# mcu1_secondary.net
KiCad netlist of a schematic drawn in Altium Designer
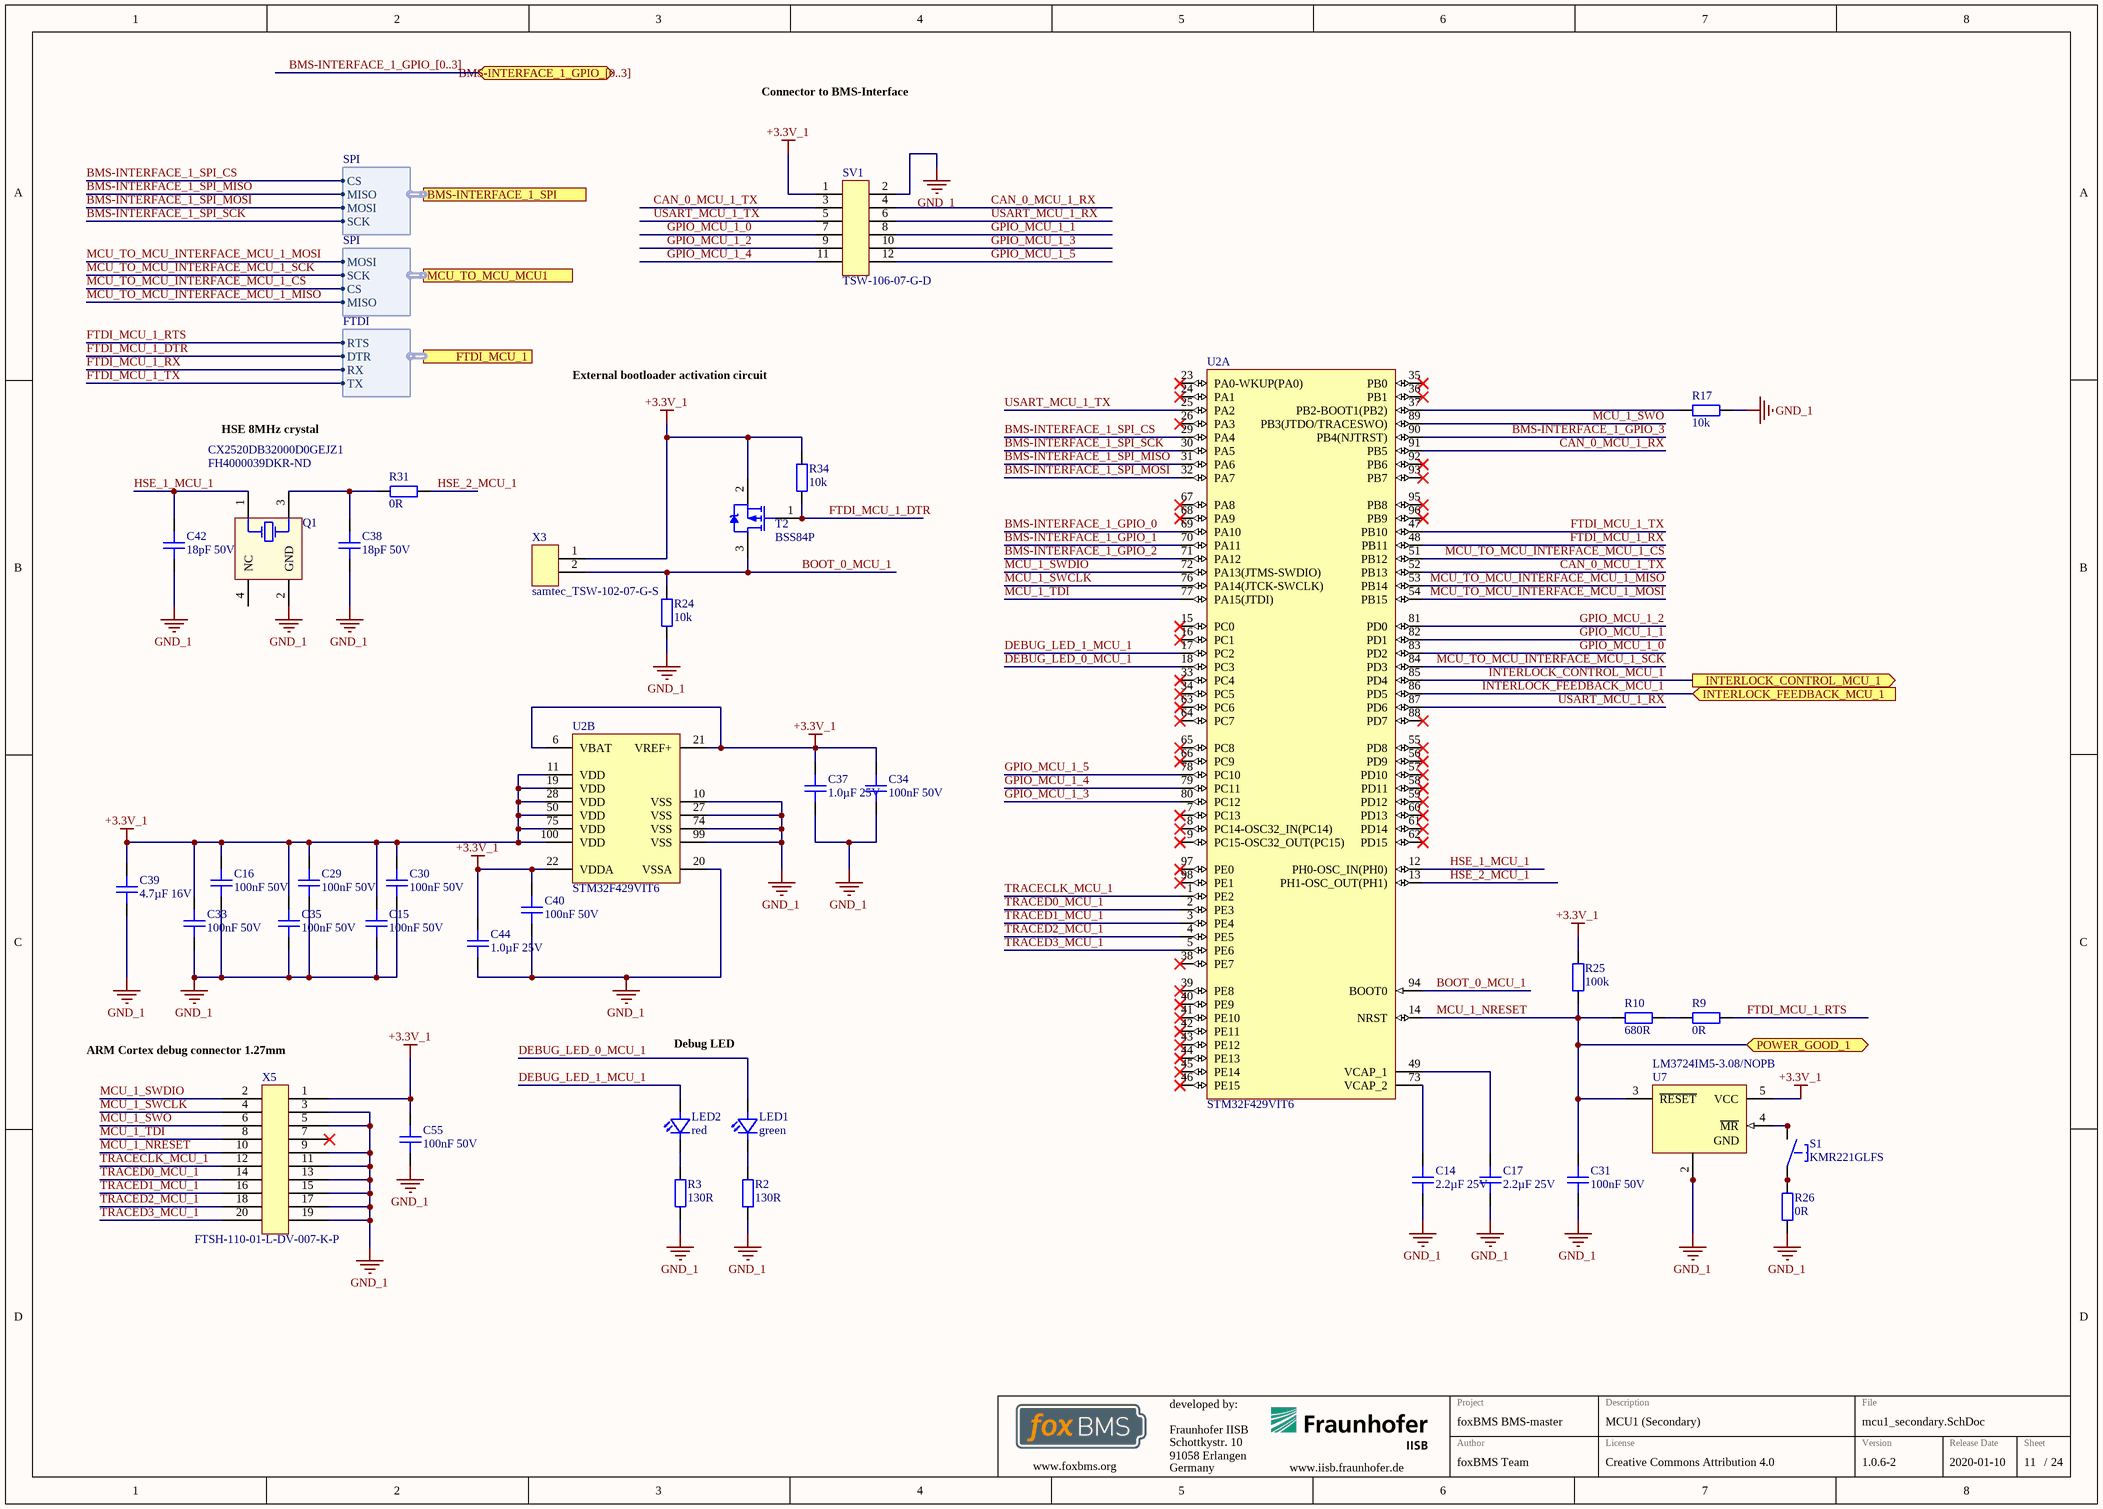
[diagram p0: mcu1_secondary.SchDoc]

(export (version "E")
  (design (tool "Eeschema 10.0.6"))
  (components
    (comp (ref "C14")
      (value "2.2µF 25V")
      (footprint "0805C")
      (description "Ceramic, 2.2µF, ±10%, 25V, X7R, –55 to 125°C, 0805 (2012),RoHS, Automotive")
      (fields (field (name "PART NUMBER") "GCJ21BR71E225KA01") (field (name "TOLERANCE") "±10%"))
      (libsource (lib "master-010106") (part "gen_C_ceramic_2u2_50V_X7R_0805"))
    )
    (comp (ref "C15")
      (value "100nF 50V")
      (footprint "0402C")
      (description "Ceramic, 100nF, ±10%, 50V, X7R, –55 to 125°C, 0402 (1005),RoHS, Automotive")
      (fields (field (name "PART NUMBER") "GCM155R71H104KE02") (field (name "TOLERANCE") "±10%"))
      (libsource (lib "master-010106") (part "gen_C_ceramic_100n_50V_X7R_0402"))
    )
    (comp (ref "C16")
      (value "100nF 50V")
      (footprint "0402C")
      (description "Ceramic, 100nF, ±10%, 50V, X7R, –55 to 125°C, 0402 (1005),RoHS, Automotive")
      (fields (field (name "PART NUMBER") "GCM155R71H104KE02") (field (name "TOLERANCE") "±10%"))
      (libsource (lib "master-010106") (part "gen_C_ceramic_100n_50V_X7R_0402"))
    )
    (comp (ref "C17")
      (value "2.2µF 25V")
      (footprint "0805C")
      (description "Ceramic, 2.2µF, ±10%, 25V, X7R, –55 to 125°C, 0805 (2012),RoHS, Automotive")
      (fields (field (name "PART NUMBER") "GCJ21BR71E225KA01") (field (name "TOLERANCE") "±10%"))
      (libsource (lib "master-010106") (part "gen_C_ceramic_2u2_50V_X7R_0805"))
    )
    (comp (ref "C29")
      (value "100nF 50V")
      (footprint "0402C")
      (description "Ceramic, 100nF, ±10%, 50V, X7R, –55 to 125°C, 0402 (1005),RoHS, Automotive")
      (fields (field (name "PART NUMBER") "GCM155R71H104KE02") (field (name "TOLERANCE") "±10%"))
      (libsource (lib "master-010106") (part "gen_C_ceramic_100n_50V_X7R_0402"))
    )
    (comp (ref "C30")
      (value "100nF 50V")
      (footprint "0402C")
      (description "Ceramic, 100nF, ±10%, 50V, X7R, –55 to 125°C, 0402 (1005),RoHS, Automotive")
      (fields (field (name "PART NUMBER") "GCM155R71H104KE02") (field (name "TOLERANCE") "±10%"))
      (libsource (lib "master-010106") (part "gen_C_ceramic_100n_50V_X7R_0402"))
    )
    (comp (ref "C31")
      (value "100nF 50V")
      (footprint "0603C")
      (description "Ceramic, 100nF, ±10%, 50V, X7R, –55 to 125°C, 0603 (1608),RoHS, Automotive")
      (fields (field (name "PART NUMBER") "GCJ188R71H104KA12") (field (name "TOLERANCE") "±10%"))
      (libsource (lib "master-010106") (part "C"))
    )
    (comp (ref "C33")
      (value "100nF 50V")
      (footprint "0402C")
      (description "Ceramic, 100nF, ±10%, 50V, X7R, –55 to 125°C, 0402 (1005),RoHS, Automotive")
      (fields (field (name "PART NUMBER") "GCM155R71H104KE02") (field (name "TOLERANCE") "±10%"))
      (libsource (lib "master-010106") (part "gen_C_ceramic_100n_50V_X7R_0402"))
    )
    (comp (ref "C34")
      (value "100nF 50V")
      (footprint "0402C")
      (description "Ceramic, 100nF, ±10%, 50V, X7R, –55 to 125°C, 0402 (1005),RoHS, Automotive")
      (fields (field (name "PART NUMBER") "GCM155R71H104KE02") (field (name "TOLERANCE") "±10%"))
      (libsource (lib "master-010106") (part "gen_C_ceramic_100n_50V_X7R_0402"))
    )
    (comp (ref "C35")
      (value "100nF 50V")
      (footprint "0402C")
      (description "Ceramic, 100nF, ±10%, 50V, X7R, –55 to 125°C, 0402 (1005),RoHS, Automotive")
      (fields (field (name "PART NUMBER") "GCM155R71H104KE02") (field (name "TOLERANCE") "±10%"))
      (libsource (lib "master-010106") (part "gen_C_ceramic_100n_50V_X7R_0402"))
    )
    (comp (ref "C37")
      (value "1.0µF 25V")
      (footprint "0603C")
      (description "Ceramic, 1.0µF, ±10%, 25V, X7R, –55 to 125°C, 0603 (1608),RoHS, Automotive")
      (fields (field (name "PART NUMBER") "GCJ188R71E105KA01") (field (name "TOLERANCE") "±10%"))
      (libsource (lib "master-010106") (part "gen_C_ceramic_1u_25V_X7R_0603"))
    )
    (comp (ref "C38")
      (value "18pF 50V")
      (footprint "0402C")
      (description "Ceramic, 18pF, ±5%, 50V, X7R, 25 to 125°C, 0402 (1005),RoHS, Automotive")
      (fields (field (name "PART NUMBER") "GCM1555C1H180JA16#") (field (name "TOLERANCE") "±5%"))
      (libsource (lib "master-010106") (part "gen_C_ceramic_18p_50V_C0G_0402"))
    )
    (comp (ref "C39")
      (value "4.7µF 16V")
      (footprint "0805C")
      (description "Ceramic, 4.7µF, ±10%, 16V, X7R, –55 to 125°C, 0805 (2012),RoHS, Automotive")
      (fields (field (name "PART NUMBER") "GCJ21BR71C475KA01") (field (name "TOLERANCE") "±10%"))
      (libsource (lib "master-010106") (part "gen_C_ceramic_4u7_16V_X7R_0805"))
    )
    (comp (ref "C40")
      (value "100nF 50V")
      (footprint "0402C")
      (description "Ceramic, 100nF, ±10%, 50V, X7R, –55 to 125°C, 0402 (1005),RoHS, Automotive")
      (fields (field (name "PART NUMBER") "GCM155R71H104KE02") (field (name "TOLERANCE") "±10%"))
      (libsource (lib "master-010106") (part "gen_C_ceramic_100n_50V_X7R_0402"))
    )
    (comp (ref "C42")
      (value "18pF 50V")
      (footprint "0402C")
      (description "Ceramic, 18pF, ±5%, 50V, X7R, 25 to 125°C, 0402 (1005),RoHS, Automotive")
      (fields (field (name "PART NUMBER") "GCM1555C1H180JA16#") (field (name "TOLERANCE") "±5%"))
      (libsource (lib "master-010106") (part "gen_C_ceramic_18p_50V_C0G_0402"))
    )
    (comp (ref "C44")
      (value "1.0µF 25V")
      (footprint "0603C")
      (description "Ceramic, 1.0µF, ±10%, 25V, X7R, –55 to 125°C, 0603 (1608),RoHS, Automotive")
      (fields (field (name "PART NUMBER") "GCJ188R71E105KA01") (field (name "TOLERANCE") "±10%"))
      (libsource (lib "master-010106") (part "gen_C_ceramic_1u_25V_X7R_0603"))
    )
    (comp (ref "C55")
      (value "100nF 50V")
      (footprint "0603C")
      (description "Ceramic, 100nF, ±10%, 50V, X7R, –55 to 125°C, 0603 (1608),RoHS, Automotive")
      (fields (field (name "PART NUMBER") "GCJ188R71H104KA12") (field (name "TOLERANCE") "±10%"))
      (libsource (lib "master-010106") (part "C"))
    )
    (comp (ref "LED1")
      (value "green")
      (footprint "LEDC1608X07N")
      (description "LED")
      (fields (field (name "PART NUMBER") "gen_LED_0603_green"))
      (libsource (lib "OE750") (part "D_LED"))
    )
    (comp (ref "LED2")
      (value "red")
      (footprint "LEDC1608X07N")
      (description "LED")
      (fields (field (name "PART NUMBER") "gen_LED_0603_red"))
      (libsource (lib "OE750") (part "D_LED"))
    )
    (comp (ref "Q1")
      (value "CX2520DB32000D0GEJZ1")
      (footprint "AVX-CX2520DB32000D0GEJZ1-4_V")
      (description "Crystal,CRYSTAL 40MHZ 15PF 85degC Surface Mount 2.5 x 2.0 mm")
      (fields
        (field (name "MANUFACTURER") "Kyocera")
        (field (name "SUPPLIER PART NUMBER 1") "FH4000039DKR-ND")
      )
      (libsource (lib "Altium Content Vault") (part "AVX-CX2520DB32000D0GEJZ1-4"))
    )
    (comp (ref "R2")
      (value "130R")
      (footprint "0603R")
      (description "SMD Resistor 130R 0603")
      (fields (field (name "PART NUMBER") "gen_R_130R_0603") (field (name "TOLERANCE") "1%"))
      (libsource (lib "master-010106") (part "R"))
    )
    (comp (ref "R3")
      (value "130R")
      (footprint "0603R")
      (description "SMD Resistor 130R 0603")
      (fields (field (name "PART NUMBER") "gen_R_130R_0603") (field (name "TOLERANCE") "1%"))
      (libsource (lib "master-010106") (part "R"))
    )
    (comp (ref "R9")
      (value "0R")
      (footprint "0603R")
      (description "SMD Resistor 0R 0603")
      (fields (field (name "PART NUMBER") "gen_R_0R_0603") (field (name "POWER") "0.1W"))
      (libsource (lib "master-010106") (part "R"))
    )
    (comp (ref "R10")
      (value "680R")
      (footprint "0603R")
      (description "SMD Resistor 680R 0603")
      (fields (field (name "PART NUMBER") "gen_R_680R_0603") (field (name "TOLERANCE") "1%"))
      (libsource (lib "master-010106") (part "R"))
    )
    (comp (ref "R17")
      (value "10k")
      (footprint "0603R")
      (description "SMD Resistor 10k 0603")
      (fields (field (name "PART NUMBER") "gen_R_10k_0603") (field (name "TOLERANCE") "1%"))
      (libsource (lib "master-010106") (part "R"))
    )
    (comp (ref "R24")
      (value "10k")
      (footprint "0603R")
      (description "SMD Resistor 10k 0603")
      (fields (field (name "PART NUMBER") "gen_R_10k_0603") (field (name "TOLERANCE") "1%"))
      (libsource (lib "master-010106") (part "R"))
    )
    (comp (ref "R25")
      (value "100k")
      (footprint "0603R")
      (description "SMD Resistor 100k 0603")
      (fields (field (name "PART NUMBER") "gen_R_100k_0603"))
      (libsource (lib "master-010106") (part "gen_R_100k_0603"))
    )
    (comp (ref "R26")
      (value "0R")
      (footprint "0603R")
      (description "SMD Resistor 0R 0603")
      (fields (field (name "PART NUMBER") "gen_R_0R_0603") (field (name "POWER") "0.1W"))
      (libsource (lib "master-010106") (part "R"))
    )
    (comp (ref "R31")
      (value "0R")
      (footprint "0402R")
      (description "SMD Resistor 0R 0402")
      (fields (field (name "PART NUMBER") "gen_R_0R_0402"))
      (libsource (lib "master-010106") (part "gen_R_0R_0402"))
    )
    (comp (ref "R34")
      (value "10k")
      (footprint "0603R")
      (description "SMD Resistor 10k 0603")
      (fields (field (name "PART NUMBER") "gen_R_10k_0603") (field (name "TOLERANCE") "1%"))
      (libsource (lib "master-010106") (part "R"))
    )
    (comp (ref "S1")
      (value "KMR221GLFS")
      (footprint "KMR2_Series")
      (description "Microminiature Tactile Switch")
      (fields (field (name "MANUFACTURER") "CK Components"))
      (libsource (lib "OE750") (part "Switch_4_Pin"))
    )
    (comp (ref "SV1")
      (value "TSW-106-07-G-D")
      (footprint "Pinheader_2.54_2x6")
      (description "Board-To-Board Connector, Vertical, 2.54 mm, 12 Contacts, Header, TSW Series, Through Hole, 2 Rows")
      (fields (field (name "MANUFACTURER") "Samtec"))
      (libsource (lib "OE750") (part "X2x6"))
    )
    (comp (ref "T2")
      (value "BSS84P")
      (footprint "INF-PG-SOT23_N")
      (fields (field (name "MANUFACTURER") "Infineon"))
      (libsource (lib "Altium Content Vault") (part "INF-PEMOS-GSD-3-B"))
    )
    (comp (ref "U2")
      (value "STM32F429VIT6")
      (footprint "STM-LQFP100_N")
      (fields (field (name "MANUFACTURER") "STMicroelectronics"))
      (libsource (lib "Altium Content Vault") (part "MC-ARM-STM32F4X9-SQ100"))
    )
    (comp (ref "U7")
      (value "LM3724IM5-3.08/NOPB")
      (footprint "MF05A_N")
      (description "5-Pin Microprocessor Reset Circuits, 5-pin SOT-23, Pb-Free")
      (fields (field (name "MANUFACTURER") "National Semiconductor"))
      (libsource (lib "Altium Content Vault") (part "PM-SCCT-LM3724-5"))
    )
    (comp (ref "X3")
      (value "samtec_TSW-102-07-G-S")
      (footprint "Pinheader_2.54_2")
      (description "Board-To-Board Connector, Vertical, 2.54 mm, 2 Contacts, Header, TSW Series, Through Hole, 1 Row")
      (fields (field (name "MANUFACTURER") "Samtec"))
      (libsource (lib "OE750") (part "X2"))
    )
    (comp (ref "X5")
      (value "FTSH-110-01-L-DV-007-K-P")
      (footprint "CORTEX_DEBUG_20_PIN")
      (description "Board-To-Board Connector, ARM Cortex Debug Header 20 Pin")
      (fields
        (field (name "PART NUMBER") "samtec_FTSH-110-01-L-DV-007-K-P")
        (field (name "MANUFACTURER") "Samtec")
      )
      (libsource (lib "OE750") (part "CORTEX_DEBUG_20_PIN"))
    )
  )
  (nets
    (net (code "3") (name "+3.3V_1") (class "Default")
      (node (ref "C15") (pin "1") (pinfunction "1_1") (pintype "passive"))
      (node (ref "C16") (pin "1") (pinfunction "1_1") (pintype "passive"))
      (node (ref "C29") (pin "1") (pinfunction "1_1") (pintype "passive"))
      (node (ref "C30") (pin "1") (pinfunction "1_1") (pintype "passive"))
      (node (ref "C33") (pin "1") (pinfunction "1_1") (pintype "passive"))
      (node (ref "C34") (pin "1") (pinfunction "1_1") (pintype "passive"))
      (node (ref "C35") (pin "1") (pinfunction "1_1") (pintype "passive"))
      (node (ref "C37") (pin "1") (pinfunction "1_1") (pintype "passive"))
      (node (ref "C39") (pin "1") (pinfunction "1_1") (pintype "passive"))
      (node (ref "C40") (pin "1") (pinfunction "1_1") (pintype "passive"))
      (node (ref "C44") (pin "1") (pinfunction "1_1") (pintype "passive"))
      (node (ref "C55") (pin "1") (pinfunction "1_1") (pintype "passive"))
      (node (ref "R25") (pin "2") (pinfunction "2_2") (pintype "passive"))
      (node (ref "R34") (pin "2") (pinfunction "2_2") (pintype "passive"))
      (node (ref "SV1") (pin "1") (pintype "passive"))
      (node (ref "T2") (pin "2") (pinfunction "SOURCE_2") (pintype "passive"))
      (node (ref "U2") (pin "100") (pinfunction "VDD_100") (pintype "power_in"))
      (node (ref "U2") (pin "11") (pinfunction "VDD_11") (pintype "power_in"))
      (node (ref "U2") (pin "19") (pinfunction "VDD_19") (pintype "power_in"))
      (node (ref "U2") (pin "21") (pinfunction "VREF+_21") (pintype "power_in"))
      (node (ref "U2") (pin "22") (pinfunction "VDDA_22") (pintype "power_in"))
      (node (ref "U2") (pin "28") (pinfunction "VDD_28") (pintype "power_in"))
      (node (ref "U2") (pin "50") (pinfunction "VDD_50") (pintype "power_in"))
      (node (ref "U2") (pin "6") (pinfunction "VBAT_6") (pintype "power_in"))
      (node (ref "U2") (pin "75") (pinfunction "VDD_75") (pintype "power_in"))
      (node (ref "U7") (pin "5") (pinfunction "VCC_5") (pintype "power_in"))
      (node (ref "X3") (pin "1") (pintype "passive"))
      (node (ref "X5") (pin "1") (pintype "passive"))
    )
    (net (code "4") (name "/BMS-INTERFACE_1_GPIO_0") (class "Default")
      (node (ref "U2") (pin "69") (pinfunction "PA10_69") (pintype "bidirectional"))
    )
    (net (code "5") (name "/BMS-INTERFACE_1_GPIO_1") (class "Default")
      (node (ref "U2") (pin "70") (pinfunction "PA11_70") (pintype "bidirectional"))
    )
    (net (code "6") (name "/BMS-INTERFACE_1_GPIO_2") (class "Default")
      (node (ref "U2") (pin "71") (pinfunction "PA12_71") (pintype "bidirectional"))
    )
    (net (code "7") (name "/BMS-INTERFACE_1_GPIO_3") (class "Default")
      (node (ref "U2") (pin "90") (pinfunction "PB4(NJTRST)_90") (pintype "bidirectional"))
    )
    (net (code "9") (name "/BMS-INTERFACE_1_SPI_CS") (class "Default")
      (node (ref "U2") (pin "29") (pinfunction "PA4_29") (pintype "bidirectional"))
    )
    (net (code "10") (name "/BMS-INTERFACE_1_SPI_MISO") (class "Default")
      (node (ref "U2") (pin "31") (pinfunction "PA6_31") (pintype "bidirectional"))
    )
    (net (code "11") (name "/BMS-INTERFACE_1_SPI_MOSI") (class "Default")
      (node (ref "U2") (pin "32") (pinfunction "PA7_32") (pintype "bidirectional"))
    )
    (net (code "12") (name "/BMS-INTERFACE_1_SPI_SCK") (class "Default")
      (node (ref "U2") (pin "30") (pinfunction "PA5_30") (pintype "bidirectional"))
    )
    (net (code "13") (name "/BOOT_0_MCU_1") (class "Default")
      (node (ref "R24") (pin "2") (pinfunction "2_2") (pintype "passive"))
      (node (ref "T2") (pin "3") (pinfunction "DRAIN_3") (pintype "passive"))
      (node (ref "U2") (pin "94") (pinfunction "BOOT0_94") (pintype "input"))
      (node (ref "X3") (pin "2") (pintype "passive"))
    )
    (net (code "14") (name "/CAN_0_MCU_1_RX") (class "Default")
      (node (ref "SV1") (pin "4") (pintype "passive"))
      (node (ref "U2") (pin "91") (pinfunction "PB5_91") (pintype "bidirectional"))
    )
    (net (code "15") (name "/CAN_0_MCU_1_TX") (class "Default")
      (node (ref "SV1") (pin "3") (pintype "passive"))
      (node (ref "U2") (pin "52") (pinfunction "PB13_52") (pintype "bidirectional"))
    )
    (net (code "16") (name "/DEBUG_LED_0_MCU_1") (class "Default")
      (node (ref "LED1") (pin "2") (pinfunction "A_2") (pintype "passive"))
      (node (ref "U2") (pin "18") (pinfunction "PC3_18") (pintype "bidirectional"))
    )
    (net (code "17") (name "/DEBUG_LED_1_MCU_1") (class "Default")
      (node (ref "LED2") (pin "2") (pinfunction "A_2") (pintype "passive"))
      (node (ref "U2") (pin "17") (pinfunction "PC2_17") (pintype "bidirectional"))
    )
    (net (code "18") (name "/FTDI_MCU_1_DTR") (class "Default")
      (node (ref "R34") (pin "1") (pinfunction "1_1") (pintype "passive"))
      (node (ref "T2") (pin "1") (pinfunction "GATE_1") (pintype "passive"))
    )
    (net (code "19") (name "/FTDI_MCU_1_RTS") (class "Default")
      (node (ref "R9") (pin "2") (pinfunction "2_2") (pintype "passive"))
    )
    (net (code "20") (name "/FTDI_MCU_1_RX") (class "Default")
      (node (ref "U2") (pin "48") (pinfunction "PB11_48") (pintype "bidirectional"))
    )
    (net (code "21") (name "/FTDI_MCU_1_TX") (class "Default")
      (node (ref "U2") (pin "47") (pinfunction "PB10_47") (pintype "bidirectional"))
    )
    (net (code "22") (name "/GPIO_MCU_1_0") (class "Default")
      (node (ref "SV1") (pin "7") (pintype "passive"))
      (node (ref "U2") (pin "83") (pinfunction "PD2_83") (pintype "bidirectional"))
    )
    (net (code "23") (name "/GPIO_MCU_1_1") (class "Default")
      (node (ref "SV1") (pin "8") (pintype "passive"))
      (node (ref "U2") (pin "82") (pinfunction "PD1_82") (pintype "bidirectional"))
    )
    (net (code "24") (name "/GPIO_MCU_1_2") (class "Default")
      (node (ref "SV1") (pin "9") (pintype "passive"))
      (node (ref "U2") (pin "81") (pinfunction "PD0_81") (pintype "bidirectional"))
    )
    (net (code "25") (name "/GPIO_MCU_1_3") (class "Default")
      (node (ref "SV1") (pin "10") (pintype "passive"))
      (node (ref "U2") (pin "80") (pinfunction "PC12_80") (pintype "bidirectional"))
    )
    (net (code "26") (name "/GPIO_MCU_1_4") (class "Default")
      (node (ref "SV1") (pin "11") (pintype "passive"))
      (node (ref "U2") (pin "79") (pinfunction "PC11_79") (pintype "bidirectional"))
    )
    (net (code "27") (name "/GPIO_MCU_1_5") (class "Default")
      (node (ref "SV1") (pin "12") (pintype "passive"))
      (node (ref "U2") (pin "78") (pinfunction "PC10_78") (pintype "bidirectional"))
    )
    (net (code "28") (name "/HSE_1_MCU_1") (class "Default")
      (node (ref "C42") (pin "2") (pinfunction "2_2") (pintype "passive"))
      (node (ref "Q1") (pin "1") (pinfunction "HOT_1") (pintype "passive"))
      (node (ref "U2") (pin "12") (pinfunction "PH0-OSC_IN(PH0)_12") (pintype "bidirectional"))
    )
    (net (code "29") (name "/HSE_2_MCU_1") (class "Default")
      (node (ref "R31") (pin "1") (pinfunction "1_1") (pintype "passive"))
      (node (ref "U2") (pin "13") (pinfunction "PH1-OSC_OUT(PH1)_13") (pintype "bidirectional"))
    )
    (net (code "30") (name "/INTERLOCK_CONTROL_MCU_1") (class "Default")
      (node (ref "U2") (pin "85") (pinfunction "PD4_85") (pintype "bidirectional"))
    )
    (net (code "31") (name "/INTERLOCK_FEEDBACK_MCU_1") (class "Default")
      (node (ref "U2") (pin "86") (pinfunction "PD5_86") (pintype "bidirectional"))
    )
    (net (code "32") (name "/MCU_1_NRESET") (class "Default")
      (node (ref "C31") (pin "1") (pinfunction "1_1") (pintype "passive"))
      (node (ref "R10") (pin "1") (pinfunction "1_1") (pintype "passive"))
      (node (ref "R25") (pin "1") (pinfunction "1_1") (pintype "passive"))
      (node (ref "U2") (pin "14") (pinfunction "NRST_14") (pintype "bidirectional"))
      (node (ref "U7") (pin "3") (pinfunction "~{RESET}_3") (pintype "open_collector"))
      (node (ref "X5") (pin "10") (pintype "passive"))
    )
    (net (code "33") (name "/MCU_1_SWCLK") (class "Default")
      (node (ref "U2") (pin "76") (pinfunction "PA14(JTCK-SWCLK)_76") (pintype "bidirectional"))
      (node (ref "X5") (pin "4") (pintype "passive"))
    )
    (net (code "34") (name "/MCU_1_SWDIO") (class "Default")
      (node (ref "U2") (pin "72") (pinfunction "PA13(JTMS-SWDIO)_72") (pintype "bidirectional"))
      (node (ref "X5") (pin "2") (pintype "passive"))
    )
    (net (code "35") (name "/MCU_1_SWO") (class "Default")
      (node (ref "U2") (pin "89") (pinfunction "PB3(JTDO/TRACESWO)_89") (pintype "bidirectional"))
      (node (ref "X5") (pin "6") (pintype "passive"))
    )
    (net (code "36") (name "/MCU_1_TDI") (class "Default")
      (node (ref "U2") (pin "77") (pinfunction "PA15(JTDI)_77") (pintype "bidirectional"))
      (node (ref "X5") (pin "8") (pintype "passive"))
    )
    (net (code "37") (name "/MCU_TO_MCU_INTERFACE_MCU_1_CS") (class "Default")
      (node (ref "U2") (pin "51") (pinfunction "PB12_51") (pintype "bidirectional"))
    )
    (net (code "38") (name "/MCU_TO_MCU_INTERFACE_MCU_1_MISO") (class "Default")
      (node (ref "U2") (pin "53") (pinfunction "PB14_53") (pintype "bidirectional"))
    )
    (net (code "39") (name "/MCU_TO_MCU_INTERFACE_MCU_1_MOSI") (class "Default")
      (node (ref "U2") (pin "54") (pinfunction "PB15_54") (pintype "bidirectional"))
    )
    (net (code "40") (name "/MCU_TO_MCU_INTERFACE_MCU_1_SCK") (class "Default")
      (node (ref "U2") (pin "84") (pinfunction "PD3_84") (pintype "bidirectional"))
    )
    (net (code "41") (name "/TRACECLK_MCU_1") (class "Default")
      (node (ref "U2") (pin "1") (pinfunction "PE2_1") (pintype "bidirectional"))
      (node (ref "X5") (pin "12") (pintype "passive"))
    )
    (net (code "42") (name "/TRACED0_MCU_1") (class "Default")
      (node (ref "U2") (pin "2") (pinfunction "PE3_2") (pintype "bidirectional"))
      (node (ref "X5") (pin "14") (pintype "passive"))
    )
    (net (code "43") (name "/TRACED1_MCU_1") (class "Default")
      (node (ref "U2") (pin "3") (pinfunction "PE4_3") (pintype "bidirectional"))
      (node (ref "X5") (pin "16") (pintype "passive"))
    )
    (net (code "44") (name "/TRACED2_MCU_1") (class "Default")
      (node (ref "U2") (pin "4") (pinfunction "PE5_4") (pintype "bidirectional"))
      (node (ref "X5") (pin "18") (pintype "passive"))
    )
    (net (code "45") (name "/TRACED3_MCU_1") (class "Default")
      (node (ref "U2") (pin "5") (pinfunction "PE6_5") (pintype "bidirectional"))
      (node (ref "X5") (pin "20") (pintype "passive"))
    )
    (net (code "46") (name "/USART_MCU_1_RX") (class "Default")
      (node (ref "SV1") (pin "6") (pintype "passive"))
      (node (ref "U2") (pin "87") (pinfunction "PD6_87") (pintype "bidirectional"))
    )
    (net (code "47") (name "/USART_MCU_1_TX") (class "Default")
      (node (ref "SV1") (pin "5") (pintype "passive"))
      (node (ref "U2") (pin "25") (pinfunction "PA2_25") (pintype "bidirectional"))
    )
    (net (code "50") (name "GND_1") (class "Default")
      (node (ref "C14") (pin "2") (pinfunction "2_2") (pintype "passive"))
      (node (ref "C15") (pin "2") (pinfunction "2_2") (pintype "passive"))
      (node (ref "C16") (pin "2") (pinfunction "2_2") (pintype "passive"))
      (node (ref "C17") (pin "2") (pinfunction "2_2") (pintype "passive"))
      (node (ref "C29") (pin "2") (pinfunction "2_2") (pintype "passive"))
      (node (ref "C30") (pin "2") (pinfunction "2_2") (pintype "passive"))
      (node (ref "C31") (pin "2") (pinfunction "2_2") (pintype "passive"))
      (node (ref "C33") (pin "2") (pinfunction "2_2") (pintype "passive"))
      (node (ref "C34") (pin "2") (pinfunction "2_2") (pintype "passive"))
      (node (ref "C35") (pin "2") (pinfunction "2_2") (pintype "passive"))
      (node (ref "C37") (pin "2") (pinfunction "2_2") (pintype "passive"))
      (node (ref "C38") (pin "2") (pinfunction "2_2") (pintype "passive"))
      (node (ref "C39") (pin "2") (pinfunction "2_2") (pintype "passive"))
      (node (ref "C40") (pin "2") (pinfunction "2_2") (pintype "passive"))
      (node (ref "C42") (pin "1") (pinfunction "1_1") (pintype "passive"))
      (node (ref "C44") (pin "2") (pinfunction "2_2") (pintype "passive"))
      (node (ref "C55") (pin "2") (pinfunction "2_2") (pintype "passive"))
      (node (ref "Q1") (pin "2") (pinfunction "GND_2") (pintype "power_in"))
      (node (ref "R17") (pin "1") (pinfunction "1_1") (pintype "passive"))
      (node (ref "R2") (pin "1") (pinfunction "1_1") (pintype "passive"))
      (node (ref "R24") (pin "1") (pinfunction "1_1") (pintype "passive"))
      (node (ref "R26") (pin "1") (pinfunction "1_1") (pintype "passive"))
      (node (ref "R3") (pin "1") (pinfunction "1_1") (pintype "passive"))
      (node (ref "SV1") (pin "2") (pintype "passive"))
      (node (ref "U2") (pin "10") (pinfunction "VSS_10") (pintype "power_in"))
      (node (ref "U2") (pin "20") (pinfunction "VSSA_20") (pintype "power_in"))
      (node (ref "U2") (pin "27") (pinfunction "VSS_27") (pintype "power_in"))
      (node (ref "U2") (pin "74") (pinfunction "VSS_74") (pintype "power_in"))
      (node (ref "U2") (pin "99") (pinfunction "VSS_99") (pintype "power_in"))
      (node (ref "U7") (pin "1") (pinfunction "GND_1") (pintype "power_in"))
      (node (ref "U7") (pin "2") (pinfunction "GND_2") (pintype "power_in"))
      (node (ref "X5") (pin "11") (pintype "passive"))
      (node (ref "X5") (pin "13") (pintype "passive"))
      (node (ref "X5") (pin "15") (pintype "passive"))
      (node (ref "X5") (pin "17") (pintype "passive"))
      (node (ref "X5") (pin "19") (pintype "passive"))
      (node (ref "X5") (pin "3") (pintype "passive"))
      (node (ref "X5") (pin "5") (pintype "passive"))
      (node (ref "X5") (pin "9") (pintype "passive"))
    )
    (net (code "51") (name "Net-(C38-Pad1)") (class "Default")
      (node (ref "C38") (pin "1") (pinfunction "1_1") (pintype "passive"))
      (node (ref "Q1") (pin "3") (pinfunction "HOT_3") (pintype "passive"))
      (node (ref "R31") (pin "2") (pinfunction "2_2") (pintype "passive"))
    )
    (net (code "52") (name "Net-(LED1-C)") (class "Default")
      (node (ref "LED1") (pin "1") (pinfunction "C_1") (pintype "passive"))
      (node (ref "R2") (pin "2") (pinfunction "2_2") (pintype "passive"))
    )
    (net (code "53") (name "Net-(LED2-C)") (class "Default")
      (node (ref "LED2") (pin "1") (pinfunction "C_1") (pintype "passive"))
      (node (ref "R3") (pin "2") (pinfunction "2_2") (pintype "passive"))
    )
    (net (code "54") (name "Net-(R10-Pad2)") (class "Default")
      (node (ref "R10") (pin "2") (pinfunction "2_2") (pintype "passive"))
      (node (ref "R9") (pin "1") (pinfunction "1_1") (pintype "passive"))
    )
    (net (code "55") (name "Net-(R26-Pad2)") (class "Default")
      (node (ref "R26") (pin "2") (pinfunction "2_2") (pintype "passive"))
      (node (ref "S1") (pin "1") (pintype "passive"))
      (node (ref "S1") (pin "2") (pintype "passive"))
    )
    (net (code "56") (name "Net-(U2A-PB2-BOOT1(PB2))") (class "Default")
      (node (ref "R17") (pin "2") (pinfunction "2_2") (pintype "passive"))
      (node (ref "U2") (pin "37") (pinfunction "PB2-BOOT1(PB2)_37") (pintype "bidirectional"))
    )
    (net (code "57") (name "Net-(U2A-VCAP_1)") (class "Default")
      (node (ref "C17") (pin "1") (pinfunction "1_1") (pintype "passive"))
      (node (ref "U2") (pin "49") (pinfunction "VCAP_1_49") (pintype "power_in"))
    )
    (net (code "58") (name "Net-(U2A-VCAP_2)") (class "Default")
      (node (ref "C14") (pin "1") (pinfunction "1_1") (pintype "passive"))
      (node (ref "U2") (pin "73") (pinfunction "VCAP_2_73") (pintype "power_in"))
    )
    (net (code "59") (name "Net-(U7-~{MR})") (class "Default")
      (node (ref "S1") (pin "3") (pintype "passive"))
      (node (ref "S1") (pin "4") (pintype "passive"))
      (node (ref "U7") (pin "4") (pinfunction "~{MR}_4") (pintype "input"))
    )
    (net (code "60") (name "unconnected-(Q1-NC-Pad4)") (class "Default")
      (node (ref "Q1") (pin "4") (pinfunction "NC_4") (pintype "passive"))
    )
    (net (code "61") (name "unconnected-(U2A-PA0-WKUP(PA0)-Pad23)") (class "Default")
      (node (ref "U2") (pin "23") (pinfunction "PA0-WKUP(PA0)_23") (pintype "bidirectional+no_connect"))
    )
    (net (code "62") (name "unconnected-(U2A-PA1-Pad24)") (class "Default")
      (node (ref "U2") (pin "24") (pinfunction "PA1_24") (pintype "bidirectional+no_connect"))
    )
    (net (code "63") (name "unconnected-(U2A-PA3-Pad26)") (class "Default")
      (node (ref "U2") (pin "26") (pinfunction "PA3_26") (pintype "bidirectional+no_connect"))
    )
    (net (code "64") (name "unconnected-(U2A-PA8-Pad67)") (class "Default")
      (node (ref "U2") (pin "67") (pinfunction "PA8_67") (pintype "bidirectional+no_connect"))
    )
    (net (code "65") (name "unconnected-(U2A-PA9-Pad68)") (class "Default")
      (node (ref "U2") (pin "68") (pinfunction "PA9_68") (pintype "bidirectional+no_connect"))
    )
    (net (code "66") (name "unconnected-(U2A-PB0-Pad35)") (class "Default")
      (node (ref "U2") (pin "35") (pinfunction "PB0_35") (pintype "bidirectional+no_connect"))
    )
    (net (code "67") (name "unconnected-(U2A-PB1-Pad36)") (class "Default")
      (node (ref "U2") (pin "36") (pinfunction "PB1_36") (pintype "bidirectional+no_connect"))
    )
    (net (code "68") (name "unconnected-(U2A-PB6-Pad92)") (class "Default")
      (node (ref "U2") (pin "92") (pinfunction "PB6_92") (pintype "bidirectional+no_connect"))
    )
    (net (code "69") (name "unconnected-(U2A-PB7-Pad93)") (class "Default")
      (node (ref "U2") (pin "93") (pinfunction "PB7_93") (pintype "bidirectional+no_connect"))
    )
    (net (code "70") (name "unconnected-(U2A-PB8-Pad95)") (class "Default")
      (node (ref "U2") (pin "95") (pinfunction "PB8_95") (pintype "bidirectional+no_connect"))
    )
    (net (code "71") (name "unconnected-(U2A-PB9-Pad96)") (class "Default")
      (node (ref "U2") (pin "96") (pinfunction "PB9_96") (pintype "bidirectional+no_connect"))
    )
    (net (code "72") (name "unconnected-(U2A-PC0-Pad15)") (class "Default")
      (node (ref "U2") (pin "15") (pinfunction "PC0_15") (pintype "bidirectional+no_connect"))
    )
    (net (code "73") (name "unconnected-(U2A-PC1-Pad16)") (class "Default")
      (node (ref "U2") (pin "16") (pinfunction "PC1_16") (pintype "bidirectional+no_connect"))
    )
    (net (code "74") (name "unconnected-(U2A-PC4-Pad33)") (class "Default")
      (node (ref "U2") (pin "33") (pinfunction "PC4_33") (pintype "bidirectional+no_connect"))
    )
    (net (code "75") (name "unconnected-(U2A-PC5-Pad34)") (class "Default")
      (node (ref "U2") (pin "34") (pinfunction "PC5_34") (pintype "bidirectional+no_connect"))
    )
    (net (code "76") (name "unconnected-(U2A-PC6-Pad63)") (class "Default")
      (node (ref "U2") (pin "63") (pinfunction "PC6_63") (pintype "bidirectional+no_connect"))
    )
    (net (code "77") (name "unconnected-(U2A-PC7-Pad64)") (class "Default")
      (node (ref "U2") (pin "64") (pinfunction "PC7_64") (pintype "bidirectional+no_connect"))
    )
    (net (code "78") (name "unconnected-(U2A-PC8-Pad65)") (class "Default")
      (node (ref "U2") (pin "65") (pinfunction "PC8_65") (pintype "bidirectional+no_connect"))
    )
    (net (code "79") (name "unconnected-(U2A-PC9-Pad66)") (class "Default")
      (node (ref "U2") (pin "66") (pinfunction "PC9_66") (pintype "bidirectional+no_connect"))
    )
    (net (code "80") (name "unconnected-(U2A-PC13-Pad7)") (class "Default")
      (node (ref "U2") (pin "7") (pinfunction "PC13_7") (pintype "bidirectional+no_connect"))
    )
    (net (code "81") (name "unconnected-(U2A-PC14-OSC32_IN(PC14)-Pad8)") (class "Default")
      (node (ref "U2") (pin "8") (pinfunction "PC14-OSC32_IN(PC14)_8") (pintype "bidirectional+no_connect"))
    )
    (net (code "82") (name "unconnected-(U2A-PC15-OSC32_OUT(PC15)-Pad9)") (class "Default")
      (node (ref "U2") (pin "9") (pinfunction "PC15-OSC32_OUT(PC15)_9") (pintype "bidirectional+no_connect"))
    )
    (net (code "83") (name "unconnected-(U2A-PD7-Pad88)") (class "Default")
      (node (ref "U2") (pin "88") (pinfunction "PD7_88") (pintype "bidirectional+no_connect"))
    )
    (net (code "84") (name "unconnected-(U2A-PD8-Pad55)") (class "Default")
      (node (ref "U2") (pin "55") (pinfunction "PD8_55") (pintype "bidirectional+no_connect"))
    )
    (net (code "85") (name "unconnected-(U2A-PD9-Pad56)") (class "Default")
      (node (ref "U2") (pin "56") (pinfunction "PD9_56") (pintype "bidirectional+no_connect"))
    )
    (net (code "86") (name "unconnected-(U2A-PD10-Pad57)") (class "Default")
      (node (ref "U2") (pin "57") (pinfunction "PD10_57") (pintype "bidirectional+no_connect"))
    )
    (net (code "87") (name "unconnected-(U2A-PD11-Pad58)") (class "Default")
      (node (ref "U2") (pin "58") (pinfunction "PD11_58") (pintype "bidirectional+no_connect"))
    )
    (net (code "88") (name "unconnected-(U2A-PD12-Pad59)") (class "Default")
      (node (ref "U2") (pin "59") (pinfunction "PD12_59") (pintype "bidirectional+no_connect"))
    )
    (net (code "89") (name "unconnected-(U2A-PD13-Pad60)") (class "Default")
      (node (ref "U2") (pin "60") (pinfunction "PD13_60") (pintype "bidirectional+no_connect"))
    )
    (net (code "90") (name "unconnected-(U2A-PD14-Pad61)") (class "Default")
      (node (ref "U2") (pin "61") (pinfunction "PD14_61") (pintype "bidirectional+no_connect"))
    )
    (net (code "91") (name "unconnected-(U2A-PD15-Pad62)") (class "Default")
      (node (ref "U2") (pin "62") (pinfunction "PD15_62") (pintype "bidirectional+no_connect"))
    )
    (net (code "92") (name "unconnected-(U2A-PE0-Pad97)") (class "Default")
      (node (ref "U2") (pin "97") (pinfunction "PE0_97") (pintype "bidirectional+no_connect"))
    )
    (net (code "93") (name "unconnected-(U2A-PE1-Pad98)") (class "Default")
      (node (ref "U2") (pin "98") (pinfunction "PE1_98") (pintype "bidirectional+no_connect"))
    )
    (net (code "94") (name "unconnected-(U2A-PE7-Pad38)") (class "Default")
      (node (ref "U2") (pin "38") (pinfunction "PE7_38") (pintype "bidirectional+no_connect"))
    )
    (net (code "95") (name "unconnected-(U2A-PE8-Pad39)") (class "Default")
      (node (ref "U2") (pin "39") (pinfunction "PE8_39") (pintype "bidirectional+no_connect"))
    )
    (net (code "96") (name "unconnected-(U2A-PE9-Pad40)") (class "Default")
      (node (ref "U2") (pin "40") (pinfunction "PE9_40") (pintype "bidirectional+no_connect"))
    )
    (net (code "97") (name "unconnected-(U2A-PE10-Pad41)") (class "Default")
      (node (ref "U2") (pin "41") (pinfunction "PE10_41") (pintype "bidirectional+no_connect"))
    )
    (net (code "98") (name "unconnected-(U2A-PE11-Pad42)") (class "Default")
      (node (ref "U2") (pin "42") (pinfunction "PE11_42") (pintype "bidirectional+no_connect"))
    )
    (net (code "99") (name "unconnected-(U2A-PE12-Pad43)") (class "Default")
      (node (ref "U2") (pin "43") (pinfunction "PE12_43") (pintype "bidirectional+no_connect"))
    )
    (net (code "100") (name "unconnected-(U2A-PE13-Pad44)") (class "Default")
      (node (ref "U2") (pin "44") (pinfunction "PE13_44") (pintype "bidirectional+no_connect"))
    )
    (net (code "101") (name "unconnected-(U2A-PE14-Pad45)") (class "Default")
      (node (ref "U2") (pin "45") (pinfunction "PE14_45") (pintype "bidirectional+no_connect"))
    )
    (net (code "102") (name "unconnected-(U2A-PE15-Pad46)") (class "Default")
      (node (ref "U2") (pin "46") (pinfunction "PE15_46") (pintype "bidirectional+no_connect"))
    )
    (net (code "103") (name "unconnected-(X5-Pad7)") (class "Default")
      (node (ref "X5") (pin "7") (pintype "passive+no_connect"))
    )
  )
)
